# STM32G4_V2.net
KiCad netlist of a schematic drawn in Altium Designer
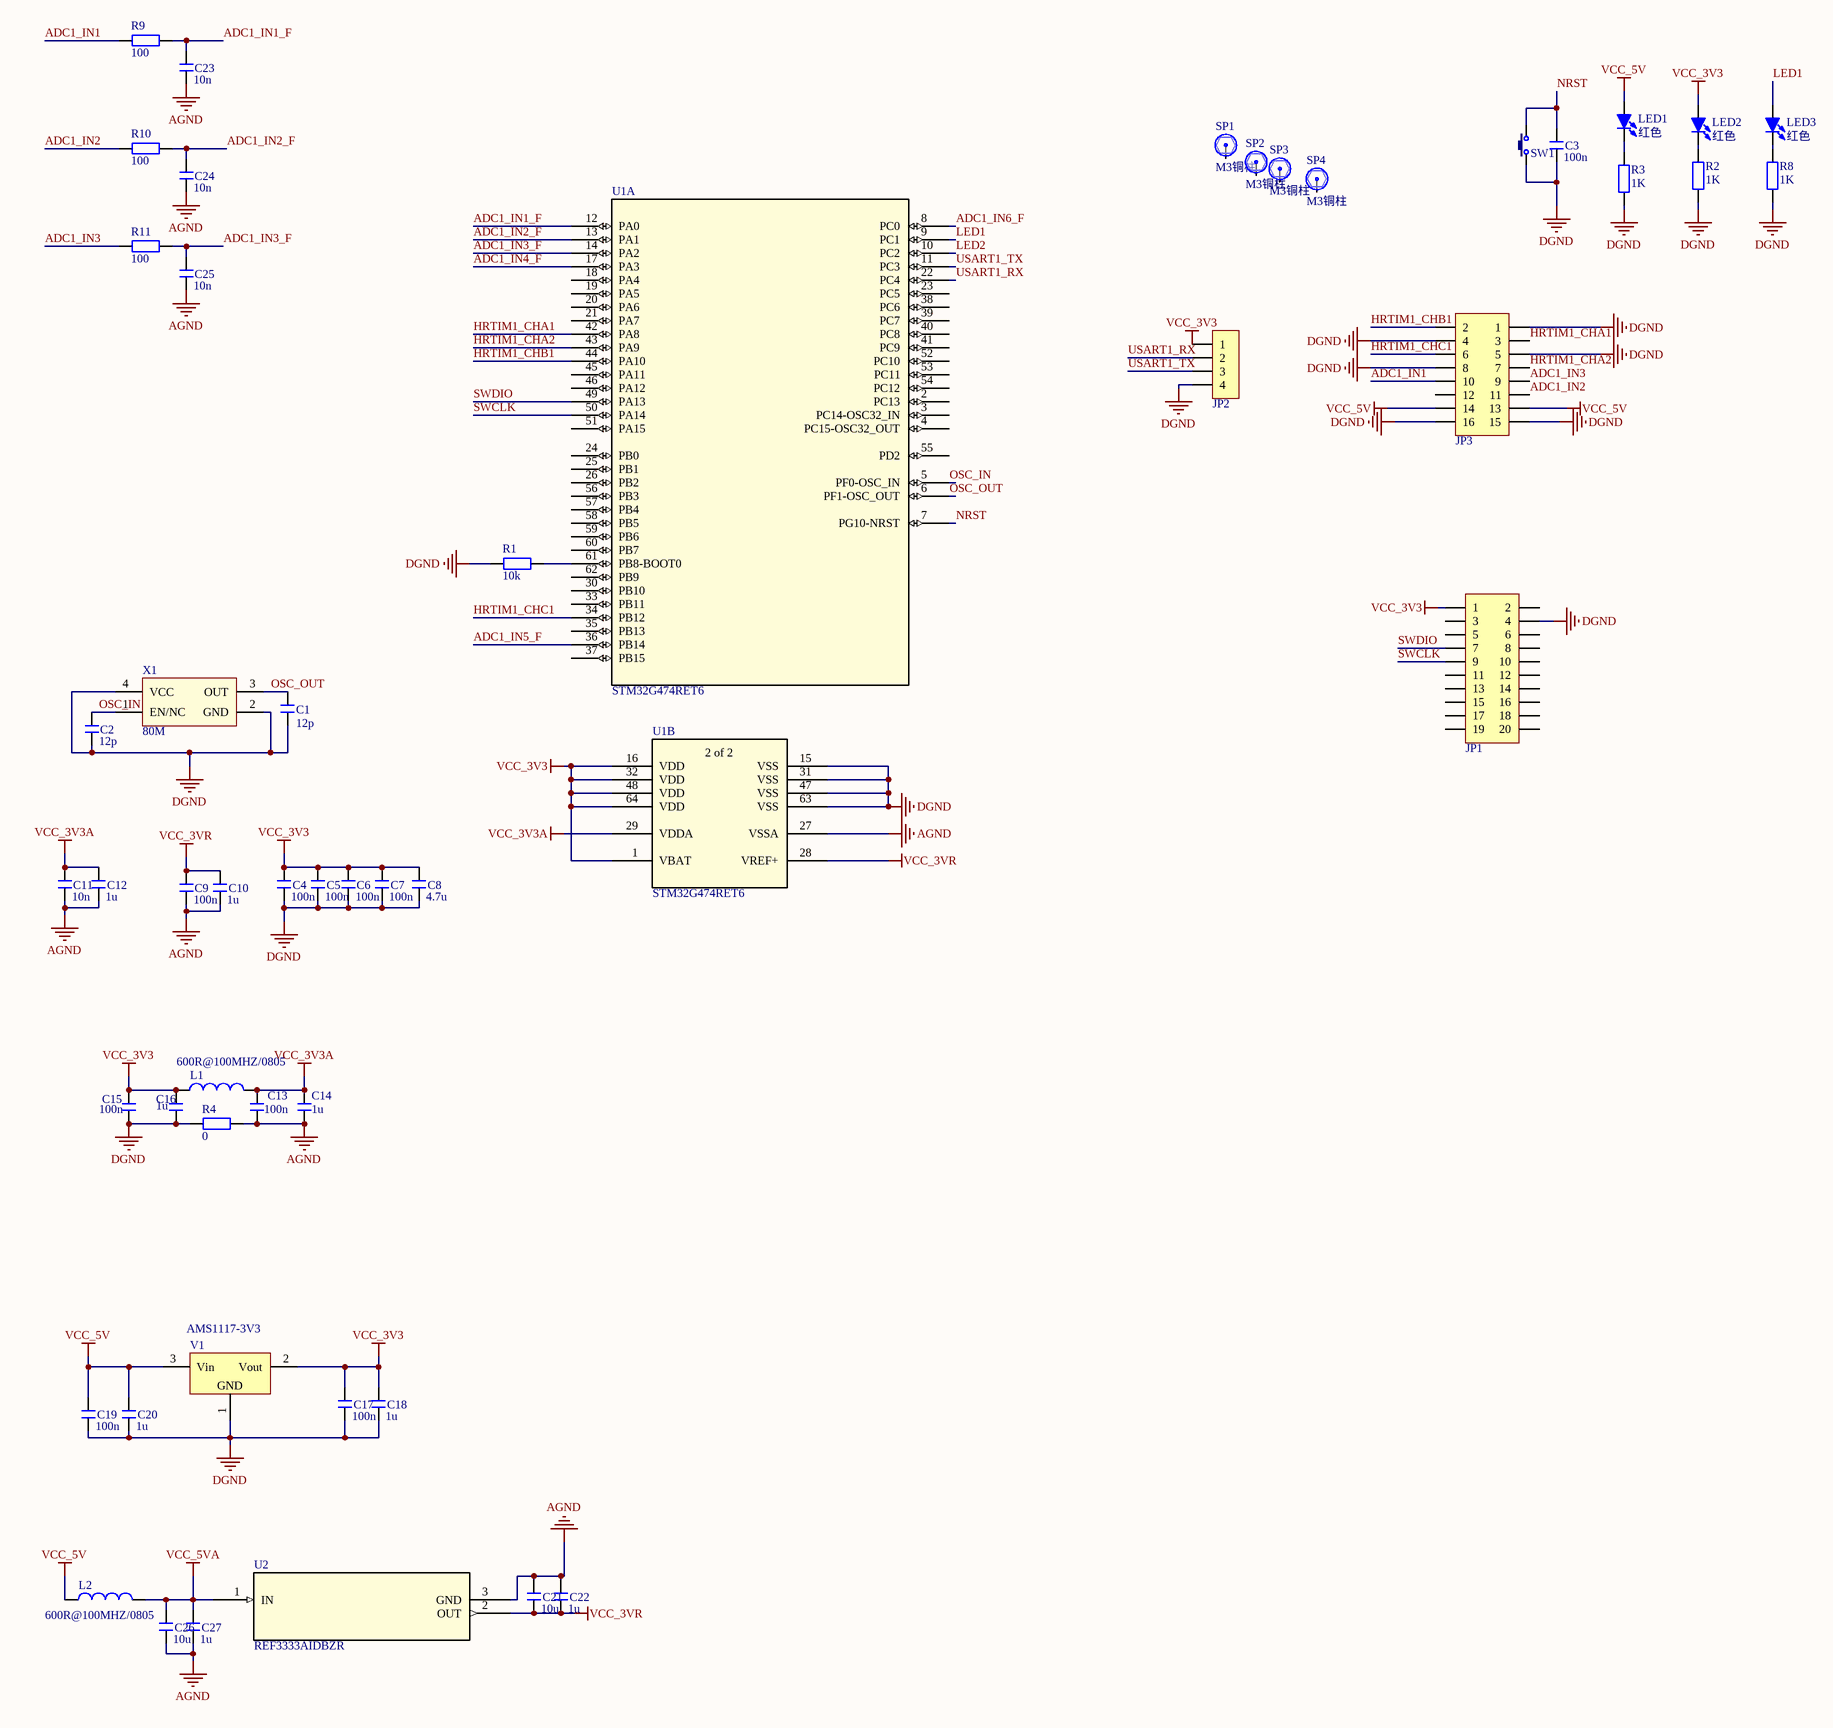
[diagram p0: STM32G4_V2.SchDoc]

(export (version "E")
  (design (tool "Eeschema 10.0.6"))
  (components
    (comp (ref "C1")
      (value "12p")
      (footprint "C 0603_L")
      (description "无极性贴片电容")
      (fields (field (name "版权归属") "源创客"))
      (libsource (lib "3.1   - 电阻-电容-电感") (part "C"))
    )
    (comp (ref "C2")
      (value "12p")
      (footprint "C 0603_L")
      (description "无极性贴片电容")
      (fields (field (name "版权归属") "源创客"))
      (libsource (lib "3.1   - 电阻-电容-电感") (part "C"))
    )
    (comp (ref "C3")
      (value "100n")
      (footprint "C 0603_L")
      (description "无极性贴片电容")
      (fields (field (name "版权归属") "源创客"))
      (libsource (lib "3.1   - 电阻-电容-电感") (part "C"))
    )
    (comp (ref "C4")
      (value "100n")
      (footprint "C 0603_L")
      (description "无极性贴片电容")
      (fields (field (name "版权归属") "源创客"))
      (libsource (lib "3.1   - 电阻-电容-电感") (part "C"))
    )
    (comp (ref "C5")
      (value "100n")
      (footprint "C 0603_L")
      (description "无极性贴片电容")
      (fields (field (name "版权归属") "源创客"))
      (libsource (lib "3.1   - 电阻-电容-电感") (part "C"))
    )
    (comp (ref "C6")
      (value "100n")
      (footprint "C 0603_L")
      (description "无极性贴片电容")
      (fields (field (name "版权归属") "源创客"))
      (libsource (lib "3.1   - 电阻-电容-电感") (part "C"))
    )
    (comp (ref "C7")
      (value "100n")
      (footprint "C 0603_L")
      (description "无极性贴片电容")
      (fields (field (name "版权归属") "源创客"))
      (libsource (lib "3.1   - 电阻-电容-电感") (part "C"))
    )
    (comp (ref "C8")
      (value "4.7u")
      (footprint "C 0603_L")
      (description "无极性贴片电容")
      (fields (field (name "版权归属") "源创客"))
      (libsource (lib "3.1   - 电阻-电容-电感") (part "C"))
    )
    (comp (ref "C9")
      (value "100n")
      (footprint "C 0603_L")
      (description "无极性贴片电容")
      (fields (field (name "版权归属") "源创客"))
      (libsource (lib "3.1   - 电阻-电容-电感") (part "C"))
    )
    (comp (ref "C10")
      (value "1u")
      (footprint "C 0603_L")
      (description "无极性贴片电容")
      (fields (field (name "版权归属") "源创客"))
      (libsource (lib "3.1   - 电阻-电容-电感") (part "C"))
    )
    (comp (ref "C11")
      (value "10n")
      (footprint "C 0603_L")
      (description "无极性贴片电容")
      (fields (field (name "版权归属") "源创客"))
      (libsource (lib "3.1   - 电阻-电容-电感") (part "C"))
    )
    (comp (ref "C12")
      (value "1u")
      (footprint "C 0603_L")
      (description "无极性贴片电容")
      (fields (field (name "版权归属") "源创客"))
      (libsource (lib "3.1   - 电阻-电容-电感") (part "C"))
    )
    (comp (ref "C13")
      (value "100n")
      (footprint "C 0603_L")
      (description "无极性贴片电容")
      (fields (field (name "版权归属") "源创客"))
      (libsource (lib "3.1   - 电阻-电容-电感") (part "C"))
    )
    (comp (ref "C14")
      (value "1u")
      (footprint "C 0603_L")
      (description "无极性贴片电容")
      (fields (field (name "版权归属") "源创客"))
      (libsource (lib "3.1   - 电阻-电容-电感") (part "C"))
    )
    (comp (ref "C15")
      (value "100n")
      (footprint "C 0603_L")
      (description "无极性贴片电容")
      (fields (field (name "版权归属") "源创客"))
      (libsource (lib "3.1   - 电阻-电容-电感") (part "C"))
    )
    (comp (ref "C16")
      (value "1u")
      (footprint "C 0603_L")
      (description "无极性贴片电容")
      (fields (field (name "版权归属") "源创客"))
      (libsource (lib "3.1   - 电阻-电容-电感") (part "C"))
    )
    (comp (ref "C17")
      (value "100n")
      (footprint "C 0603_L")
      (description "无极性贴片电容")
      (fields (field (name "版权归属") "源创客"))
      (libsource (lib "3.1   - 电阻-电容-电感") (part "C"))
    )
    (comp (ref "C18")
      (value "1u")
      (footprint "C 0603_L")
      (description "无极性贴片电容")
      (fields (field (name "版权归属") "源创客"))
      (libsource (lib "3.1   - 电阻-电容-电感") (part "C"))
    )
    (comp (ref "C19")
      (value "100n")
      (footprint "C 0603_L")
      (description "无极性贴片电容")
      (fields (field (name "版权归属") "源创客"))
      (libsource (lib "3.1   - 电阻-电容-电感") (part "C"))
    )
    (comp (ref "C20")
      (value "1u")
      (footprint "C 0603_L")
      (description "无极性贴片电容")
      (fields (field (name "版权归属") "源创客"))
      (libsource (lib "3.1   - 电阻-电容-电感") (part "C"))
    )
    (comp (ref "C21")
      (value "10u")
      (footprint "C 0603_L")
      (description "无极性贴片电容")
      (fields (field (name "版权归属") "源创客"))
      (libsource (lib "3.1   - 电阻-电容-电感") (part "C"))
    )
    (comp (ref "C22")
      (value "1u")
      (footprint "C 0603_L")
      (description "无极性贴片电容")
      (fields (field (name "版权归属") "源创客"))
      (libsource (lib "3.1   - 电阻-电容-电感") (part "C"))
    )
    (comp (ref "C23")
      (value "10n")
      (footprint "C 0603_L")
      (description "无极性贴片电容")
      (fields (field (name "版权归属") "源创客"))
      (libsource (lib "3.1   - 电阻-电容-电感") (part "C"))
    )
    (comp (ref "C24")
      (value "10n")
      (footprint "C 0603_L")
      (description "无极性贴片电容")
      (fields (field (name "版权归属") "源创客"))
      (libsource (lib "3.1   - 电阻-电容-电感") (part "C"))
    )
    (comp (ref "C25")
      (value "10n")
      (footprint "C 0603_L")
      (description "无极性贴片电容")
      (fields (field (name "版权归属") "源创客"))
      (libsource (lib "3.1   - 电阻-电容-电感") (part "C"))
    )
    (comp (ref "C26")
      (value "10u")
      (footprint "C 0603_L")
      (description "无极性贴片电容")
      (fields (field (name "版权归属") "源创客"))
      (libsource (lib "3.1   - 电阻-电容-电感") (part "C"))
    )
    (comp (ref "C27")
      (value "1u")
      (footprint "C 0603_L")
      (description "无极性贴片电容")
      (fields (field (name "版权归属") "源创客"))
      (libsource (lib "3.1   - 电阻-电容-电感") (part "C"))
    )
    (comp (ref "JP1")
      (value "Header 2X10")
      (footprint "IDC2.54-LI-2x10P")
      (description "10*2P接插件")
      (fields (field (name "版权归属") "源创客"))
      (libsource (lib "4.6   - 接插件-脚距2.54") (part "Header 10X2"))
    )
    (comp (ref "JP2")
      (value "HDR-1X4")
      (footprint "XH2.54-LI-4P")
      (description "4P接插件")
      (fields (field (name "版权归属") "源创客"))
      (libsource (lib "4.6   - 接插件-脚距2.54") (part "Header 4"))
    )
    (comp (ref "JP3")
      (value "Header 8X2")
      (footprint "HDR2.54-WI-2x8P")
      (description "8*2P接插件")
      (fields (field (name "版权归属") "源创客"))
      (libsource (lib "4.6   - 接插件-脚距2.54") (part "Header 8X2"))
    )
    (comp (ref "L1")
      (value "600R@100MHZ/0805")
      (footprint "L 0805_L")
      (description "小功率贴片电感")
      (fields (field (name "版权归属") "源创客"))
      (libsource (lib "3.1   - 电阻-电容-电感") (part "L"))
    )
    (comp (ref "L2")
      (value "600R@100MHZ/0805")
      (footprint "L 0805_L")
      (description "小功率贴片电感")
      (fields (field (name "版权归属") "源创客"))
      (libsource (lib "3.1   - 电阻-电容-电感") (part "L"))
    )
    (comp (ref "LED1")
      (value "红色")
      (footprint "LED 0805G")
      (description "贴片LED")
      (fields (field (name "版权归属") "源创客"))
      (libsource (lib "9.1   - LED") (part "LED-SMD"))
    )
    (comp (ref "LED2")
      (value "红色")
      (footprint "LED 0805G")
      (description "贴片LED")
      (fields (field (name "版权归属") "源创客"))
      (libsource (lib "9.1   - LED") (part "LED-SMD"))
    )
    (comp (ref "LED3")
      (value "红色")
      (footprint "LED 0805G")
      (description "贴片LED")
      (fields (field (name "版权归属") "源创客"))
      (libsource (lib "9.1   - LED") (part "LED-SMD"))
    )
    (comp (ref "R1")
      (value "10k")
      (footprint "R 0603_L")
      (description "贴片电阻")
      (fields (field (name "版权归属") "源创客"))
      (libsource (lib "3.1   - 电阻-电容-电感") (part "R"))
    )
    (comp (ref "R2")
      (value "1K")
      (footprint "R 0603_L")
      (description "贴片电阻")
      (fields (field (name "版权归属") "源创客"))
      (libsource (lib "3.1   - 电阻-电容-电感") (part "R"))
    )
    (comp (ref "R3")
      (value "1K")
      (footprint "R 0603_L")
      (description "贴片电阻")
      (fields (field (name "版权归属") "源创客"))
      (libsource (lib "3.1   - 电阻-电容-电感") (part "R"))
    )
    (comp (ref "R4")
      (value "0")
      (footprint "R 0603_L")
      (description "贴片电阻")
      (fields (field (name "版权归属") "源创客"))
      (libsource (lib "3.1   - 电阻-电容-电感") (part "R"))
    )
    (comp (ref "R8")
      (value "1K")
      (footprint "R 0603_L")
      (description "贴片电阻")
      (fields (field (name "版权归属") "源创客"))
      (libsource (lib "3.1   - 电阻-电容-电感") (part "R"))
    )
    (comp (ref "R9")
      (value "100")
      (footprint "R 0603_L")
      (description "贴片电阻")
      (fields (field (name "版权归属") "源创客"))
      (libsource (lib "3.1   - 电阻-电容-电感") (part "R"))
    )
    (comp (ref "R10")
      (value "100")
      (footprint "R 0603_L")
      (description "贴片电阻")
      (fields (field (name "版权归属") "源创客"))
      (libsource (lib "3.1   - 电阻-电容-电感") (part "R"))
    )
    (comp (ref "R11")
      (value "100")
      (footprint "R 0603_L")
      (description "贴片电阻")
      (fields (field (name "版权归属") "源创客"))
      (libsource (lib "3.1   - 电阻-电容-电感") (part "R"))
    )
    (comp (ref "SP1")
      (value "M3铜柱")
      (footprint "M3x4_L")
      (description "铜柱")
      (fields (field (name "版权归属") "源创客"))
      (libsource (lib "15.1 - 未分类器件") (part "铜柱小焊盘"))
    )
    (comp (ref "SP2")
      (value "M3铜柱")
      (footprint "M3x4_L")
      (description "铜柱")
      (fields (field (name "版权归属") "源创客"))
      (libsource (lib "15.1 - 未分类器件") (part "铜柱小焊盘"))
    )
    (comp (ref "SP3")
      (value "M3铜柱")
      (footprint "M3x4_L")
      (description "铜柱")
      (fields (field (name "版权归属") "源创客"))
      (libsource (lib "15.1 - 未分类器件") (part "铜柱小焊盘"))
    )
    (comp (ref "SP4")
      (value "M3铜柱")
      (footprint "M3x4_L")
      (description "铜柱")
      (fields (field (name "版权归属") "源创客"))
      (libsource (lib "15.1 - 未分类器件") (part "铜柱小焊盘"))
    )
    (comp (ref "SW1")
      (value "3x6x5")
      (footprint "TSW SMD-3*6*2.5")
      (description "3x6轻触开关")
      (fields (field (name "版权归属") "源创客"))
      (libsource (lib "5.1   - 按键-开关") (part "TSW 3x6"))
    )
    (comp (ref "U1")
      (value "STM32G474RET6")
      (footprint "LQFP64-10x10mm")
      (description "No Description Available")
      (libsource (lib "STM32G474RET6") (part "STM32G474RET6"))
    )
    (comp (ref "U2")
      (value "REF3333AIDBZR")
      (footprint "DBZ3")
      (description "No Description Available")
      (libsource (lib "REF3333AIDBZR") (part "REF3333AIDBZR"))
    )
    (comp (ref "V1")
      (value "AMS1117-3V3")
      (footprint "SOT223_L")
      (description "三端稳压芯片")
      (fields (field (name "版权归属") "源创客"))
      (libsource (lib "1.3   - 电源类芯片") (part "AMS1117"))
    )
    (comp (ref "X1")
      (value "80M")
      (footprint "OSC 3225-4P")
      (description "4脚有源晶振")
      (fields (field (name "版权归属") "源创客"))
      (libsource (lib "10.1 - 保险丝-晶振") (part "XTAL-ACT-4P"))
    )
  )
  (nets
    (net (code "1") (name "/ADC1_IN1") (class "Default")
      (node (ref "JP3") (pin "10") (pinfunction "10_10") (pintype "passive"))
      (node (ref "R9") (pin "2") (pinfunction "2_2") (pintype "passive"))
    )
    (net (code "2") (name "/ADC1_IN1_F") (class "Default")
      (node (ref "C23") (pin "1") (pinfunction "1_1") (pintype "passive"))
      (node (ref "R9") (pin "1") (pinfunction "1_1") (pintype "passive"))
      (node (ref "U1") (pin "12") (pinfunction "PA0_12") (pintype "bidirectional"))
    )
    (net (code "3") (name "/ADC1_IN2") (class "Default")
      (node (ref "JP3") (pin "11") (pinfunction "11_11") (pintype "passive"))
      (node (ref "R10") (pin "2") (pinfunction "2_2") (pintype "passive"))
    )
    (net (code "4") (name "/ADC1_IN2_F") (class "Default")
      (node (ref "C24") (pin "1") (pinfunction "1_1") (pintype "passive"))
      (node (ref "R10") (pin "1") (pinfunction "1_1") (pintype "passive"))
      (node (ref "U1") (pin "13") (pinfunction "PA1_13") (pintype "bidirectional"))
    )
    (net (code "5") (name "/ADC1_IN3") (class "Default")
      (node (ref "JP3") (pin "9") (pinfunction "9_9") (pintype "passive"))
      (node (ref "R11") (pin "2") (pinfunction "2_2") (pintype "passive"))
    )
    (net (code "6") (name "/ADC1_IN3_F") (class "Default")
      (node (ref "C25") (pin "1") (pinfunction "1_1") (pintype "passive"))
      (node (ref "R11") (pin "1") (pinfunction "1_1") (pintype "passive"))
      (node (ref "U1") (pin "14") (pinfunction "PA2_14") (pintype "bidirectional"))
    )
    (net (code "7") (name "/ADC1_IN4_F") (class "Default")
      (node (ref "U1") (pin "17") (pinfunction "PA3_17") (pintype "bidirectional"))
    )
    (net (code "8") (name "/ADC1_IN5_F") (class "Default")
      (node (ref "U1") (pin "36") (pinfunction "PB14_36") (pintype "bidirectional"))
    )
    (net (code "9") (name "/ADC1_IN6_F") (class "Default")
      (node (ref "U1") (pin "8") (pinfunction "PC0_8") (pintype "bidirectional"))
    )
    (net (code "10") (name "/HRTIM1_CHA1") (class "Default")
      (node (ref "JP3") (pin "3") (pinfunction "3_3") (pintype "passive"))
      (node (ref "U1") (pin "42") (pinfunction "PA8_42") (pintype "bidirectional"))
    )
    (net (code "11") (name "/HRTIM1_CHA2") (class "Default")
      (node (ref "JP3") (pin "7") (pinfunction "7_7") (pintype "passive"))
      (node (ref "U1") (pin "43") (pinfunction "PA9_43") (pintype "bidirectional"))
    )
    (net (code "12") (name "/HRTIM1_CHB1") (class "Default")
      (node (ref "JP3") (pin "2") (pinfunction "2_2") (pintype "passive"))
      (node (ref "U1") (pin "44") (pinfunction "PA10_44") (pintype "bidirectional"))
    )
    (net (code "13") (name "/HRTIM1_CHC1") (class "Default")
      (node (ref "JP3") (pin "6") (pinfunction "6_6") (pintype "passive"))
      (node (ref "U1") (pin "34") (pinfunction "PB12_34") (pintype "bidirectional"))
    )
    (net (code "14") (name "/LED1") (class "Default")
      (node (ref "LED3") (pin "1") (pinfunction "A_1") (pintype "passive"))
      (node (ref "U1") (pin "9") (pinfunction "PC1_9") (pintype "bidirectional"))
    )
    (net (code "15") (name "/LED2") (class "Default")
      (node (ref "U1") (pin "10") (pinfunction "PC2_10") (pintype "bidirectional"))
    )
    (net (code "16") (name "/NRST") (class "Default")
      (node (ref "C3") (pin "1") (pinfunction "1_1") (pintype "passive"))
      (node (ref "SW1") (pin "2") (pinfunction "2_2") (pintype "passive"))
      (node (ref "U1") (pin "7") (pinfunction "PG10-NRST_7") (pintype "bidirectional"))
    )
    (net (code "17") (name "/OSC_IN") (class "Default")
      (node (ref "C2") (pin "1") (pinfunction "1_1") (pintype "passive"))
      (node (ref "U1") (pin "5") (pinfunction "PF0-OSC_IN_5") (pintype "bidirectional"))
      (node (ref "X1") (pin "1") (pinfunction "EN/NC_1") (pintype "passive"))
    )
    (net (code "18") (name "/OSC_OUT") (class "Default")
      (node (ref "C1") (pin "2") (pinfunction "2_2") (pintype "passive"))
      (node (ref "U1") (pin "6") (pinfunction "PF1-OSC_OUT_6") (pintype "bidirectional"))
      (node (ref "X1") (pin "3") (pinfunction "OUT_3") (pintype "passive"))
    )
    (net (code "19") (name "/SWCLK") (class "Default")
      (node (ref "JP1") (pin "9") (pinfunction "9_9") (pintype "passive"))
      (node (ref "U1") (pin "50") (pinfunction "PA14_50") (pintype "bidirectional"))
    )
    (net (code "20") (name "/SWDIO") (class "Default")
      (node (ref "JP1") (pin "7") (pinfunction "7_7") (pintype "passive"))
      (node (ref "U1") (pin "49") (pinfunction "PA13_49") (pintype "bidirectional"))
    )
    (net (code "21") (name "/USART1_RX") (class "Default")
      (node (ref "JP2") (pin "2") (pinfunction "2_2") (pintype "passive"))
      (node (ref "U1") (pin "22") (pinfunction "PC4_22") (pintype "bidirectional"))
    )
    (net (code "22") (name "/USART1_TX") (class "Default")
      (node (ref "JP2") (pin "3") (pinfunction "3_3") (pintype "passive"))
      (node (ref "U1") (pin "11") (pinfunction "PC3_11") (pintype "bidirectional"))
    )
    (net (code "23") (name "AGND") (class "Default")
      (node (ref "C10") (pin "2") (pinfunction "2_2") (pintype "passive"))
      (node (ref "C11") (pin "2") (pinfunction "2_2") (pintype "passive"))
      (node (ref "C12") (pin "2") (pinfunction "2_2") (pintype "passive"))
      (node (ref "C13") (pin "2") (pinfunction "2_2") (pintype "passive"))
      (node (ref "C14") (pin "2") (pinfunction "2_2") (pintype "passive"))
      (node (ref "C21") (pin "1") (pinfunction "1_1") (pintype "passive"))
      (node (ref "C22") (pin "1") (pinfunction "1_1") (pintype "passive"))
      (node (ref "C23") (pin "2") (pinfunction "2_2") (pintype "passive"))
      (node (ref "C24") (pin "2") (pinfunction "2_2") (pintype "passive"))
      (node (ref "C25") (pin "2") (pinfunction "2_2") (pintype "passive"))
      (node (ref "C26") (pin "2") (pinfunction "2_2") (pintype "passive"))
      (node (ref "C27") (pin "2") (pinfunction "2_2") (pintype "passive"))
      (node (ref "C9") (pin "2") (pinfunction "2_2") (pintype "passive"))
      (node (ref "R4") (pin "1") (pinfunction "1_1") (pintype "passive"))
      (node (ref "U1") (pin "27") (pinfunction "VSSA_27") (pintype "power_in"))
      (node (ref "U2") (pin "3") (pinfunction "GND_3") (pintype "power_in"))
    )
    (net (code "24") (name "DGND") (class "Default")
      (node (ref "C1") (pin "1") (pinfunction "1_1") (pintype "passive"))
      (node (ref "C15") (pin "2") (pinfunction "2_2") (pintype "passive"))
      (node (ref "C16") (pin "2") (pinfunction "2_2") (pintype "passive"))
      (node (ref "C17") (pin "2") (pinfunction "2_2") (pintype "passive"))
      (node (ref "C18") (pin "2") (pinfunction "2_2") (pintype "passive"))
      (node (ref "C19") (pin "2") (pinfunction "2_2") (pintype "passive"))
      (node (ref "C2") (pin "2") (pinfunction "2_2") (pintype "passive"))
      (node (ref "C20") (pin "2") (pinfunction "2_2") (pintype "passive"))
      (node (ref "C3") (pin "2") (pinfunction "2_2") (pintype "passive"))
      (node (ref "C4") (pin "2") (pinfunction "2_2") (pintype "passive"))
      (node (ref "C5") (pin "2") (pinfunction "2_2") (pintype "passive"))
      (node (ref "C6") (pin "2") (pinfunction "2_2") (pintype "passive"))
      (node (ref "C7") (pin "2") (pinfunction "2_2") (pintype "passive"))
      (node (ref "C8") (pin "2") (pinfunction "2_2") (pintype "passive"))
      (node (ref "JP1") (pin "4") (pinfunction "4_4") (pintype "passive"))
      (node (ref "JP2") (pin "4") (pinfunction "4_4") (pintype "passive"))
      (node (ref "JP3") (pin "1") (pinfunction "1_1") (pintype "passive"))
      (node (ref "JP3") (pin "15") (pinfunction "15_15") (pintype "passive"))
      (node (ref "JP3") (pin "16") (pinfunction "16_16") (pintype "passive"))
      (node (ref "JP3") (pin "4") (pinfunction "4_4") (pintype "passive"))
      (node (ref "JP3") (pin "5") (pinfunction "5_5") (pintype "passive"))
      (node (ref "JP3") (pin "8") (pinfunction "8_8") (pintype "passive"))
      (node (ref "R1") (pin "2") (pinfunction "2_2") (pintype "passive"))
      (node (ref "R2") (pin "1") (pinfunction "1_1") (pintype "passive"))
      (node (ref "R3") (pin "1") (pinfunction "1_1") (pintype "passive"))
      (node (ref "R4") (pin "2") (pinfunction "2_2") (pintype "passive"))
      (node (ref "R8") (pin "1") (pinfunction "1_1") (pintype "passive"))
      (node (ref "SW1") (pin "1") (pinfunction "1_1") (pintype "passive"))
      (node (ref "U1") (pin "15") (pinfunction "VSS_15") (pintype "power_in"))
      (node (ref "U1") (pin "31") (pinfunction "VSS_31") (pintype "power_in"))
      (node (ref "U1") (pin "47") (pinfunction "VSS_47") (pintype "power_in"))
      (node (ref "U1") (pin "63") (pinfunction "VSS_63") (pintype "power_in"))
      (node (ref "V1") (pin "1") (pinfunction "GND_1") (pintype "passive"))
      (node (ref "X1") (pin "2") (pinfunction "GND_2") (pintype "passive"))
      (node (ref "X1") (pin "4") (pinfunction "VCC_4") (pintype "passive"))
    )
    (net (code "25") (name "Net-(LED1-K)") (class "Default")
      (node (ref "LED1") (pin "2") (pinfunction "K_2") (pintype "passive"))
      (node (ref "R3") (pin "2") (pinfunction "2_2") (pintype "passive"))
    )
    (net (code "26") (name "Net-(LED2-K)") (class "Default")
      (node (ref "LED2") (pin "2") (pinfunction "K_2") (pintype "passive"))
      (node (ref "R2") (pin "2") (pinfunction "2_2") (pintype "passive"))
    )
    (net (code "27") (name "Net-(LED3-K)") (class "Default")
      (node (ref "LED3") (pin "2") (pinfunction "K_2") (pintype "passive"))
      (node (ref "R8") (pin "2") (pinfunction "2_2") (pintype "passive"))
    )
    (net (code "28") (name "Net-(U1A-PB8-BOOT0)") (class "Default")
      (node (ref "R1") (pin "1") (pinfunction "1_1") (pintype "passive"))
      (node (ref "U1") (pin "61") (pinfunction "PB8-BOOT0_61") (pintype "bidirectional"))
    )
    (net (code "29") (name "VCC_3V3") (class "Default")
      (node (ref "C15") (pin "1") (pinfunction "1_1") (pintype "passive"))
      (node (ref "C16") (pin "1") (pinfunction "1_1") (pintype "passive"))
      (node (ref "C17") (pin "1") (pinfunction "1_1") (pintype "passive"))
      (node (ref "C18") (pin "1") (pinfunction "1_1") (pintype "passive"))
      (node (ref "C4") (pin "1") (pinfunction "1_1") (pintype "passive"))
      (node (ref "C5") (pin "1") (pinfunction "1_1") (pintype "passive"))
      (node (ref "C6") (pin "1") (pinfunction "1_1") (pintype "passive"))
      (node (ref "C7") (pin "1") (pinfunction "1_1") (pintype "passive"))
      (node (ref "C8") (pin "1") (pinfunction "1_1") (pintype "passive"))
      (node (ref "JP1") (pin "1") (pinfunction "1_1") (pintype "passive"))
      (node (ref "JP2") (pin "1") (pinfunction "1_1") (pintype "passive"))
      (node (ref "L1") (pin "1") (pinfunction "1_1") (pintype "passive"))
      (node (ref "LED2") (pin "1") (pinfunction "A_1") (pintype "passive"))
      (node (ref "U1") (pin "1") (pinfunction "VBAT_1") (pintype "power_in"))
      (node (ref "U1") (pin "16") (pinfunction "VDD_16") (pintype "power_in"))
      (node (ref "U1") (pin "32") (pinfunction "VDD_32") (pintype "power_in"))
      (node (ref "U1") (pin "48") (pinfunction "VDD_48") (pintype "power_in"))
      (node (ref "U1") (pin "64") (pinfunction "VDD_64") (pintype "power_in"))
      (node (ref "V1") (pin "2") (pinfunction "Vout_2") (pintype "passive"))
    )
    (net (code "30") (name "VCC_3V3A") (class "Default")
      (node (ref "C11") (pin "1") (pinfunction "1_1") (pintype "passive"))
      (node (ref "C12") (pin "1") (pinfunction "1_1") (pintype "passive"))
      (node (ref "C13") (pin "1") (pinfunction "1_1") (pintype "passive"))
      (node (ref "C14") (pin "1") (pinfunction "1_1") (pintype "passive"))
      (node (ref "L1") (pin "2") (pinfunction "2_2") (pintype "passive"))
      (node (ref "U1") (pin "29") (pinfunction "VDDA_29") (pintype "power_in"))
    )
    (net (code "31") (name "VCC_3VR") (class "Default")
      (node (ref "C10") (pin "1") (pinfunction "1_1") (pintype "passive"))
      (node (ref "C21") (pin "2") (pinfunction "2_2") (pintype "passive"))
      (node (ref "C22") (pin "2") (pinfunction "2_2") (pintype "passive"))
      (node (ref "C9") (pin "1") (pinfunction "1_1") (pintype "passive"))
      (node (ref "U1") (pin "28") (pinfunction "VREF+_28") (pintype "power_in"))
      (node (ref "U2") (pin "2") (pinfunction "OUT_2") (pintype "output"))
    )
    (net (code "32") (name "VCC_5V") (class "Default")
      (node (ref "C19") (pin "1") (pinfunction "1_1") (pintype "passive"))
      (node (ref "C20") (pin "1") (pinfunction "1_1") (pintype "passive"))
      (node (ref "JP3") (pin "13") (pinfunction "13_13") (pintype "passive"))
      (node (ref "JP3") (pin "14") (pinfunction "14_14") (pintype "passive"))
      (node (ref "L2") (pin "1") (pinfunction "1_1") (pintype "passive"))
      (node (ref "LED1") (pin "1") (pinfunction "A_1") (pintype "passive"))
      (node (ref "V1") (pin "3") (pinfunction "Vin_3") (pintype "passive"))
    )
    (net (code "33") (name "VCC_5VA") (class "Default")
      (node (ref "C26") (pin "1") (pinfunction "1_1") (pintype "passive"))
      (node (ref "C27") (pin "1") (pinfunction "1_1") (pintype "passive"))
      (node (ref "L2") (pin "2") (pinfunction "2_2") (pintype "passive"))
      (node (ref "U2") (pin "1") (pinfunction "IN_1") (pintype "input"))
    )
    (net (code "34") (name "unconnected-(JP1-Pad2)") (class "Default")
      (node (ref "JP1") (pin "2") (pinfunction "2_2") (pintype "passive"))
    )
    (net (code "35") (name "unconnected-(JP1-Pad3)") (class "Default")
      (node (ref "JP1") (pin "3") (pinfunction "3_3") (pintype "passive"))
    )
    (net (code "36") (name "unconnected-(JP1-Pad5)") (class "Default")
      (node (ref "JP1") (pin "5") (pinfunction "5_5") (pintype "passive"))
    )
    (net (code "37") (name "unconnected-(JP1-Pad6)") (class "Default")
      (node (ref "JP1") (pin "6") (pinfunction "6_6") (pintype "passive"))
    )
    (net (code "38") (name "unconnected-(JP1-Pad8)") (class "Default")
      (node (ref "JP1") (pin "8") (pinfunction "8_8") (pintype "passive"))
    )
    (net (code "39") (name "unconnected-(JP1-Pad10)") (class "Default")
      (node (ref "JP1") (pin "10") (pinfunction "10_10") (pintype "passive"))
    )
    (net (code "40") (name "unconnected-(JP1-Pad11)") (class "Default")
      (node (ref "JP1") (pin "11") (pinfunction "11_11") (pintype "passive"))
    )
    (net (code "41") (name "unconnected-(JP1-Pad12)") (class "Default")
      (node (ref "JP1") (pin "12") (pinfunction "12_12") (pintype "passive"))
    )
    (net (code "42") (name "unconnected-(JP1-Pad13)") (class "Default")
      (node (ref "JP1") (pin "13") (pinfunction "13_13") (pintype "passive"))
    )
    (net (code "43") (name "unconnected-(JP1-Pad14)") (class "Default")
      (node (ref "JP1") (pin "14") (pinfunction "14_14") (pintype "passive"))
    )
    (net (code "44") (name "unconnected-(JP1-Pad15)") (class "Default")
      (node (ref "JP1") (pin "15") (pinfunction "15_15") (pintype "passive"))
    )
    (net (code "45") (name "unconnected-(JP1-Pad16)") (class "Default")
      (node (ref "JP1") (pin "16") (pinfunction "16_16") (pintype "passive"))
    )
    (net (code "46") (name "unconnected-(JP1-Pad17)") (class "Default")
      (node (ref "JP1") (pin "17") (pinfunction "17_17") (pintype "passive"))
    )
    (net (code "47") (name "unconnected-(JP1-Pad18)") (class "Default")
      (node (ref "JP1") (pin "18") (pinfunction "18_18") (pintype "passive"))
    )
    (net (code "48") (name "unconnected-(JP1-Pad19)") (class "Default")
      (node (ref "JP1") (pin "19") (pinfunction "19_19") (pintype "passive"))
    )
    (net (code "49") (name "unconnected-(JP1-Pad20)") (class "Default")
      (node (ref "JP1") (pin "20") (pinfunction "20_20") (pintype "passive"))
    )
    (net (code "50") (name "unconnected-(JP3-Pad12)") (class "Default")
      (node (ref "JP3") (pin "12") (pinfunction "12_12") (pintype "passive"))
    )
    (net (code "51") (name "unconnected-(SP1-Pad1)") (class "Default")
      (node (ref "SP1") (pin "1") (pinfunction "1_1") (pintype "passive"))
    )
    (net (code "52") (name "unconnected-(SP2-Pad1)") (class "Default")
      (node (ref "SP2") (pin "1") (pinfunction "1_1") (pintype "passive"))
    )
    (net (code "53") (name "unconnected-(SP3-Pad1)") (class "Default")
      (node (ref "SP3") (pin "1") (pinfunction "1_1") (pintype "passive"))
    )
    (net (code "54") (name "unconnected-(SP4-Pad1)") (class "Default")
      (node (ref "SP4") (pin "1") (pinfunction "1_1") (pintype "passive"))
    )
    (net (code "55") (name "unconnected-(U1A-PA4-Pad18)") (class "Default")
      (node (ref "U1") (pin "18") (pinfunction "PA4_18") (pintype "bidirectional"))
    )
    (net (code "56") (name "unconnected-(U1A-PA5-Pad19)") (class "Default")
      (node (ref "U1") (pin "19") (pinfunction "PA5_19") (pintype "bidirectional"))
    )
    (net (code "57") (name "unconnected-(U1A-PA6-Pad20)") (class "Default")
      (node (ref "U1") (pin "20") (pinfunction "PA6_20") (pintype "bidirectional"))
    )
    (net (code "58") (name "unconnected-(U1A-PA7-Pad21)") (class "Default")
      (node (ref "U1") (pin "21") (pinfunction "PA7_21") (pintype "bidirectional"))
    )
    (net (code "59") (name "unconnected-(U1A-PA11-Pad45)") (class "Default")
      (node (ref "U1") (pin "45") (pinfunction "PA11_45") (pintype "bidirectional"))
    )
    (net (code "60") (name "unconnected-(U1A-PA12-Pad46)") (class "Default")
      (node (ref "U1") (pin "46") (pinfunction "PA12_46") (pintype "bidirectional"))
    )
    (net (code "61") (name "unconnected-(U1A-PA15-Pad51)") (class "Default")
      (node (ref "U1") (pin "51") (pinfunction "PA15_51") (pintype "bidirectional"))
    )
    (net (code "62") (name "unconnected-(U1A-PB0-Pad24)") (class "Default")
      (node (ref "U1") (pin "24") (pinfunction "PB0_24") (pintype "bidirectional"))
    )
    (net (code "63") (name "unconnected-(U1A-PB1-Pad25)") (class "Default")
      (node (ref "U1") (pin "25") (pinfunction "PB1_25") (pintype "bidirectional"))
    )
    (net (code "64") (name "unconnected-(U1A-PB2-Pad26)") (class "Default")
      (node (ref "U1") (pin "26") (pinfunction "PB2_26") (pintype "bidirectional"))
    )
    (net (code "65") (name "unconnected-(U1A-PB3-Pad56)") (class "Default")
      (node (ref "U1") (pin "56") (pinfunction "PB3_56") (pintype "bidirectional"))
    )
    (net (code "66") (name "unconnected-(U1A-PB4-Pad57)") (class "Default")
      (node (ref "U1") (pin "57") (pinfunction "PB4_57") (pintype "bidirectional"))
    )
    (net (code "67") (name "unconnected-(U1A-PB5-Pad58)") (class "Default")
      (node (ref "U1") (pin "58") (pinfunction "PB5_58") (pintype "bidirectional"))
    )
    (net (code "68") (name "unconnected-(U1A-PB6-Pad59)") (class "Default")
      (node (ref "U1") (pin "59") (pinfunction "PB6_59") (pintype "bidirectional"))
    )
    (net (code "69") (name "unconnected-(U1A-PB7-Pad60)") (class "Default")
      (node (ref "U1") (pin "60") (pinfunction "PB7_60") (pintype "bidirectional"))
    )
    (net (code "70") (name "unconnected-(U1A-PB9-Pad62)") (class "Default")
      (node (ref "U1") (pin "62") (pinfunction "PB9_62") (pintype "bidirectional"))
    )
    (net (code "71") (name "unconnected-(U1A-PB10-Pad30)") (class "Default")
      (node (ref "U1") (pin "30") (pinfunction "PB10_30") (pintype "bidirectional"))
    )
    (net (code "72") (name "unconnected-(U1A-PB11-Pad33)") (class "Default")
      (node (ref "U1") (pin "33") (pinfunction "PB11_33") (pintype "bidirectional"))
    )
    (net (code "73") (name "unconnected-(U1A-PB13-Pad35)") (class "Default")
      (node (ref "U1") (pin "35") (pinfunction "PB13_35") (pintype "bidirectional"))
    )
    (net (code "74") (name "unconnected-(U1A-PB15-Pad37)") (class "Default")
      (node (ref "U1") (pin "37") (pinfunction "PB15_37") (pintype "bidirectional"))
    )
    (net (code "75") (name "unconnected-(U1A-PC5-Pad23)") (class "Default")
      (node (ref "U1") (pin "23") (pinfunction "PC5_23") (pintype "bidirectional"))
    )
    (net (code "76") (name "unconnected-(U1A-PC6-Pad38)") (class "Default")
      (node (ref "U1") (pin "38") (pinfunction "PC6_38") (pintype "bidirectional"))
    )
    (net (code "77") (name "unconnected-(U1A-PC7-Pad39)") (class "Default")
      (node (ref "U1") (pin "39") (pinfunction "PC7_39") (pintype "bidirectional"))
    )
    (net (code "78") (name "unconnected-(U1A-PC8-Pad40)") (class "Default")
      (node (ref "U1") (pin "40") (pinfunction "PC8_40") (pintype "bidirectional"))
    )
    (net (code "79") (name "unconnected-(U1A-PC9-Pad41)") (class "Default")
      (node (ref "U1") (pin "41") (pinfunction "PC9_41") (pintype "bidirectional"))
    )
    (net (code "80") (name "unconnected-(U1A-PC10-Pad52)") (class "Default")
      (node (ref "U1") (pin "52") (pinfunction "PC10_52") (pintype "bidirectional"))
    )
    (net (code "81") (name "unconnected-(U1A-PC11-Pad53)") (class "Default")
      (node (ref "U1") (pin "53") (pinfunction "PC11_53") (pintype "bidirectional"))
    )
    (net (code "82") (name "unconnected-(U1A-PC12-Pad54)") (class "Default")
      (node (ref "U1") (pin "54") (pinfunction "PC12_54") (pintype "bidirectional"))
    )
    (net (code "83") (name "unconnected-(U1A-PC13-Pad2)") (class "Default")
      (node (ref "U1") (pin "2") (pinfunction "PC13_2") (pintype "bidirectional"))
    )
    (net (code "84") (name "unconnected-(U1A-PC14-OSC32_IN-Pad3)") (class "Default")
      (node (ref "U1") (pin "3") (pinfunction "PC14-OSC32_IN_3") (pintype "bidirectional"))
    )
    (net (code "85") (name "unconnected-(U1A-PC15-OSC32_OUT-Pad4)") (class "Default")
      (node (ref "U1") (pin "4") (pinfunction "PC15-OSC32_OUT_4") (pintype "bidirectional"))
    )
    (net (code "86") (name "unconnected-(U1A-PD2-Pad55)") (class "Default")
      (node (ref "U1") (pin "55") (pinfunction "PD2_55") (pintype "bidirectional"))
    )
  )
)
